# Top.net
KiCad netlist of a schematic drawn in Altium Designer
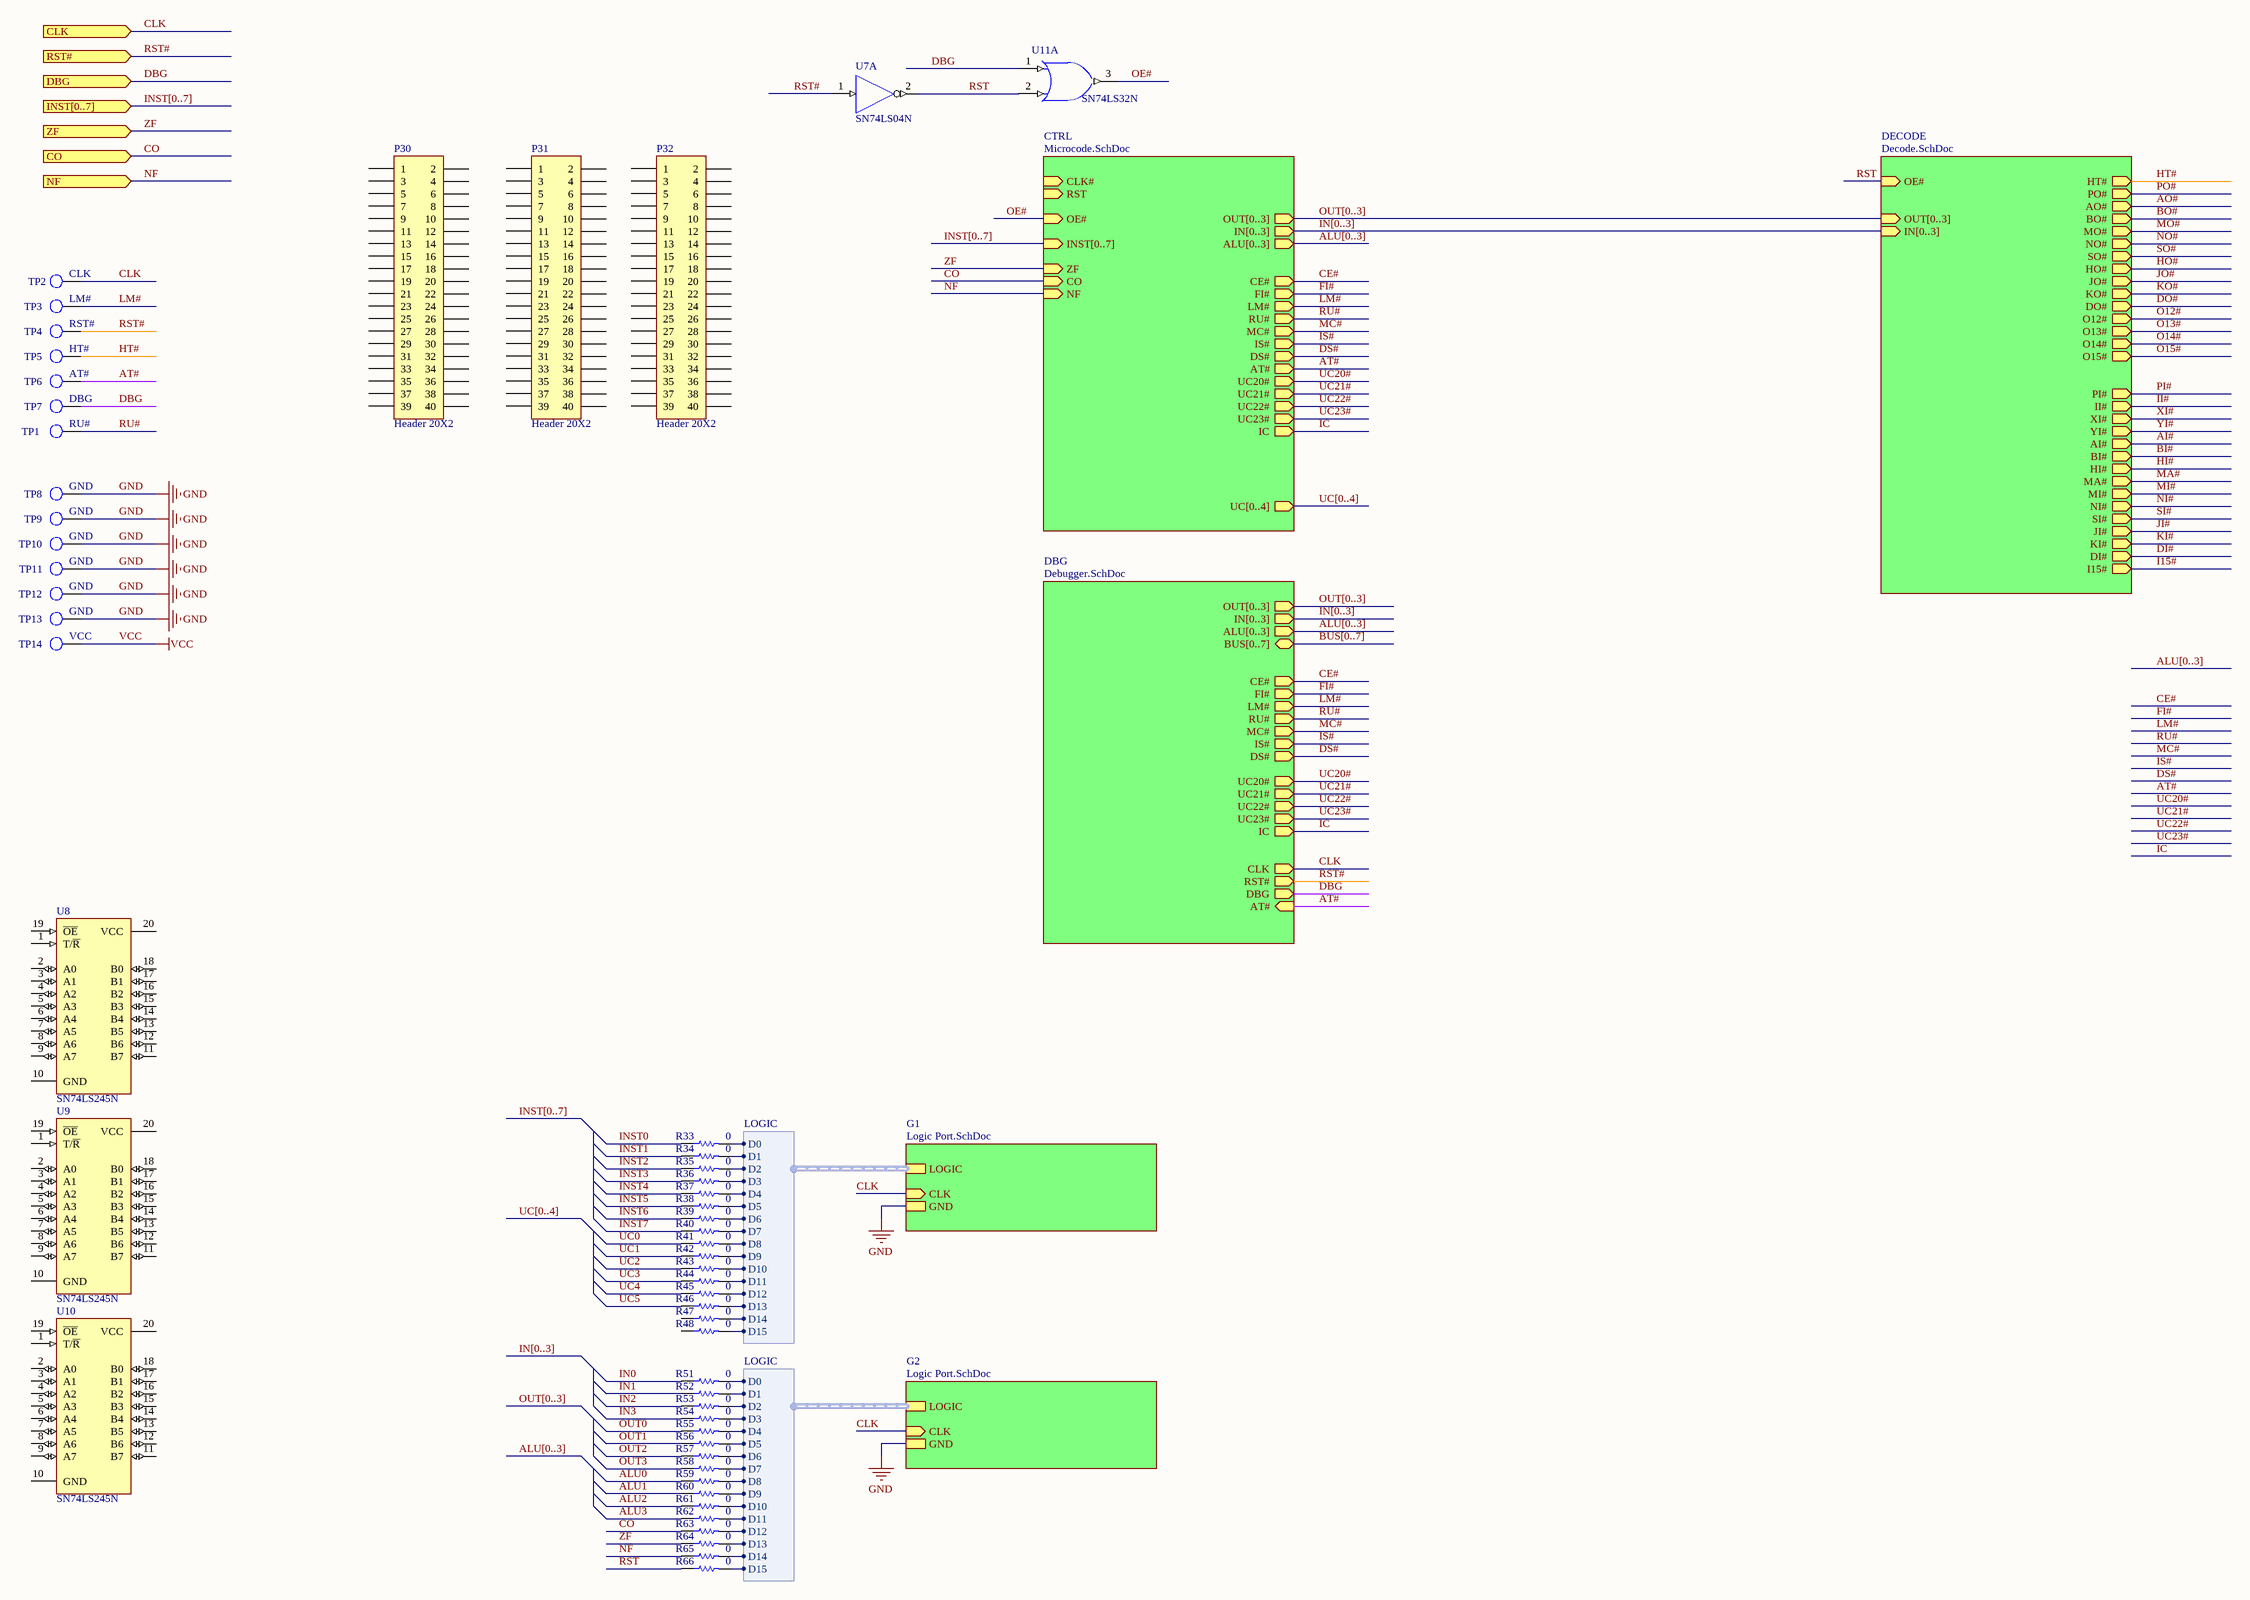
[diagram p0: Top.SchDoc]

(export (version "E")
  (design (tool "Eeschema 10.0.6"))
  (components
    (comp (ref "P30")
      (value "Header 20X2")
      (footprint "HDR2X20")
      (description "Header, 20-Pin, Dual row")
      (fields (field (name "PUBLISHER") "Altium Limited"))
      (libsource (lib "Miscellaneous Connectors") (part "Header 20X2"))
    )
    (comp (ref "P31")
      (value "Header 20X2")
      (footprint "HDR2X20")
      (description "Header, 20-Pin, Dual row")
      (fields (field (name "PUBLISHER") "Altium Limited"))
      (libsource (lib "Miscellaneous Connectors") (part "Header 20X2"))
    )
    (comp (ref "P32")
      (value "Header 20X2")
      (footprint "HDR2X20")
      (description "Header, 20-Pin, Dual row")
      (fields (field (name "PUBLISHER") "Altium Limited"))
      (libsource (lib "Miscellaneous Connectors") (part "Header 20X2"))
    )
    (comp (ref "R33")
      (value "0")
      (footprint "AXIAL-0.3")
      (description "Resistor")
      (fields (field (name "Comment") "Res1") (field (name "PUBLISHER") "Altium Limited"))
      (libsource (lib "Miscellaneous Devices") (part "Res1"))
    )
    (comp (ref "R34")
      (value "0")
      (footprint "AXIAL-0.3")
      (description "Resistor")
      (fields (field (name "Comment") "Res1") (field (name "PUBLISHER") "Altium Limited"))
      (libsource (lib "Miscellaneous Devices") (part "Res1"))
    )
    (comp (ref "R35")
      (value "0")
      (footprint "AXIAL-0.3")
      (description "Resistor")
      (fields (field (name "Comment") "Res1") (field (name "PUBLISHER") "Altium Limited"))
      (libsource (lib "Miscellaneous Devices") (part "Res1"))
    )
    (comp (ref "R36")
      (value "0")
      (footprint "AXIAL-0.3")
      (description "Resistor")
      (fields (field (name "Comment") "Res1") (field (name "PUBLISHER") "Altium Limited"))
      (libsource (lib "Miscellaneous Devices") (part "Res1"))
    )
    (comp (ref "R37")
      (value "0")
      (footprint "AXIAL-0.3")
      (description "Resistor")
      (fields (field (name "Comment") "Res1") (field (name "PUBLISHER") "Altium Limited"))
      (libsource (lib "Miscellaneous Devices") (part "Res1"))
    )
    (comp (ref "R38")
      (value "0")
      (footprint "AXIAL-0.3")
      (description "Resistor")
      (fields (field (name "Comment") "Res1") (field (name "PUBLISHER") "Altium Limited"))
      (libsource (lib "Miscellaneous Devices") (part "Res1"))
    )
    (comp (ref "R39")
      (value "0")
      (footprint "AXIAL-0.3")
      (description "Resistor")
      (fields (field (name "Comment") "Res1") (field (name "PUBLISHER") "Altium Limited"))
      (libsource (lib "Miscellaneous Devices") (part "Res1"))
    )
    (comp (ref "R40")
      (value "0")
      (footprint "AXIAL-0.3")
      (description "Resistor")
      (fields (field (name "Comment") "Res1") (field (name "PUBLISHER") "Altium Limited"))
      (libsource (lib "Miscellaneous Devices") (part "Res1"))
    )
    (comp (ref "R41")
      (value "0")
      (footprint "AXIAL-0.3")
      (description "Resistor")
      (fields (field (name "Comment") "Res1") (field (name "PUBLISHER") "Altium Limited"))
      (libsource (lib "Miscellaneous Devices") (part "Res1"))
    )
    (comp (ref "R42")
      (value "0")
      (footprint "AXIAL-0.3")
      (description "Resistor")
      (fields (field (name "Comment") "Res1") (field (name "PUBLISHER") "Altium Limited"))
      (libsource (lib "Miscellaneous Devices") (part "Res1"))
    )
    (comp (ref "R43")
      (value "0")
      (footprint "AXIAL-0.3")
      (description "Resistor")
      (fields (field (name "Comment") "Res1") (field (name "PUBLISHER") "Altium Limited"))
      (libsource (lib "Miscellaneous Devices") (part "Res1"))
    )
    (comp (ref "R44")
      (value "0")
      (footprint "AXIAL-0.3")
      (description "Resistor")
      (fields (field (name "Comment") "Res1") (field (name "PUBLISHER") "Altium Limited"))
      (libsource (lib "Miscellaneous Devices") (part "Res1"))
    )
    (comp (ref "R45")
      (value "0")
      (footprint "AXIAL-0.3")
      (description "Resistor")
      (fields (field (name "Comment") "Res1") (field (name "PUBLISHER") "Altium Limited"))
      (libsource (lib "Miscellaneous Devices") (part "Res1"))
    )
    (comp (ref "R46")
      (value "0")
      (footprint "AXIAL-0.3")
      (description "Resistor")
      (fields (field (name "Comment") "Res1") (field (name "PUBLISHER") "Altium Limited"))
      (libsource (lib "Miscellaneous Devices") (part "Res1"))
    )
    (comp (ref "R47")
      (value "0")
      (footprint "AXIAL-0.3")
      (description "Resistor")
      (fields (field (name "Comment") "Res1") (field (name "PUBLISHER") "Altium Limited"))
      (libsource (lib "Miscellaneous Devices") (part "Res1"))
    )
    (comp (ref "R48")
      (value "0")
      (footprint "AXIAL-0.3")
      (description "Resistor")
      (fields (field (name "Comment") "Res1") (field (name "PUBLISHER") "Altium Limited"))
      (libsource (lib "Miscellaneous Devices") (part "Res1"))
    )
    (comp (ref "R51")
      (value "0")
      (footprint "AXIAL-0.3")
      (description "Resistor")
      (fields (field (name "Comment") "Res1") (field (name "PUBLISHER") "Altium Limited"))
      (libsource (lib "Miscellaneous Devices") (part "Res1"))
    )
    (comp (ref "R52")
      (value "0")
      (footprint "AXIAL-0.3")
      (description "Resistor")
      (fields (field (name "Comment") "Res1") (field (name "PUBLISHER") "Altium Limited"))
      (libsource (lib "Miscellaneous Devices") (part "Res1"))
    )
    (comp (ref "R53")
      (value "0")
      (footprint "AXIAL-0.3")
      (description "Resistor")
      (fields (field (name "Comment") "Res1") (field (name "PUBLISHER") "Altium Limited"))
      (libsource (lib "Miscellaneous Devices") (part "Res1"))
    )
    (comp (ref "R54")
      (value "0")
      (footprint "AXIAL-0.3")
      (description "Resistor")
      (fields (field (name "Comment") "Res1") (field (name "PUBLISHER") "Altium Limited"))
      (libsource (lib "Miscellaneous Devices") (part "Res1"))
    )
    (comp (ref "R55")
      (value "0")
      (footprint "AXIAL-0.3")
      (description "Resistor")
      (fields (field (name "Comment") "Res1") (field (name "PUBLISHER") "Altium Limited"))
      (libsource (lib "Miscellaneous Devices") (part "Res1"))
    )
    (comp (ref "R56")
      (value "0")
      (footprint "AXIAL-0.3")
      (description "Resistor")
      (fields (field (name "Comment") "Res1") (field (name "PUBLISHER") "Altium Limited"))
      (libsource (lib "Miscellaneous Devices") (part "Res1"))
    )
    (comp (ref "R57")
      (value "0")
      (footprint "AXIAL-0.3")
      (description "Resistor")
      (fields (field (name "Comment") "Res1") (field (name "PUBLISHER") "Altium Limited"))
      (libsource (lib "Miscellaneous Devices") (part "Res1"))
    )
    (comp (ref "R58")
      (value "0")
      (footprint "AXIAL-0.3")
      (description "Resistor")
      (fields (field (name "Comment") "Res1") (field (name "PUBLISHER") "Altium Limited"))
      (libsource (lib "Miscellaneous Devices") (part "Res1"))
    )
    (comp (ref "R59")
      (value "0")
      (footprint "AXIAL-0.3")
      (description "Resistor")
      (fields (field (name "Comment") "Res1") (field (name "PUBLISHER") "Altium Limited"))
      (libsource (lib "Miscellaneous Devices") (part "Res1"))
    )
    (comp (ref "R60")
      (value "0")
      (footprint "AXIAL-0.3")
      (description "Resistor")
      (fields (field (name "Comment") "Res1") (field (name "PUBLISHER") "Altium Limited"))
      (libsource (lib "Miscellaneous Devices") (part "Res1"))
    )
    (comp (ref "R61")
      (value "0")
      (footprint "AXIAL-0.3")
      (description "Resistor")
      (fields (field (name "Comment") "Res1") (field (name "PUBLISHER") "Altium Limited"))
      (libsource (lib "Miscellaneous Devices") (part "Res1"))
    )
    (comp (ref "R62")
      (value "0")
      (footprint "AXIAL-0.3")
      (description "Resistor")
      (fields (field (name "Comment") "Res1") (field (name "PUBLISHER") "Altium Limited"))
      (libsource (lib "Miscellaneous Devices") (part "Res1"))
    )
    (comp (ref "R63")
      (value "0")
      (footprint "AXIAL-0.3")
      (description "Resistor")
      (fields (field (name "Comment") "Res1") (field (name "PUBLISHER") "Altium Limited"))
      (libsource (lib "Miscellaneous Devices") (part "Res1"))
    )
    (comp (ref "R64")
      (value "0")
      (footprint "AXIAL-0.3")
      (description "Resistor")
      (fields (field (name "Comment") "Res1") (field (name "PUBLISHER") "Altium Limited"))
      (libsource (lib "Miscellaneous Devices") (part "Res1"))
    )
    (comp (ref "R65")
      (value "0")
      (footprint "AXIAL-0.3")
      (description "Resistor")
      (fields (field (name "Comment") "Res1") (field (name "PUBLISHER") "Altium Limited"))
      (libsource (lib "Miscellaneous Devices") (part "Res1"))
    )
    (comp (ref "R66")
      (value "0")
      (footprint "AXIAL-0.3")
      (description "Resistor")
      (fields (field (name "Comment") "Res1") (field (name "PUBLISHER") "Altium Limited"))
      (libsource (lib "Miscellaneous Devices") (part "Res1"))
    )
    (comp (ref "TP1") (value "RU#") (footprint "KSTN-5011_V") (libsource (lib "TP") (part "TP")))
    (comp (ref "TP2") (value "CLK") (footprint "KSTN-5011_V") (libsource (lib "TP") (part "TP")))
    (comp (ref "TP3") (value "LM#") (footprint "KSTN-5011_V") (libsource (lib "TP") (part "TP")))
    (comp (ref "TP4") (value "RST#") (footprint "KSTN-5011_V") (libsource (lib "TP") (part "TP")))
    (comp (ref "TP5") (value "HT#") (footprint "KSTN-5011_V") (libsource (lib "TP") (part "TP")))
    (comp (ref "TP6") (value "AT#") (footprint "KSTN-5011_V") (libsource (lib "TP") (part "TP")))
    (comp (ref "TP7") (value "DBG") (footprint "KSTN-5011_V") (libsource (lib "TP") (part "TP")))
    (comp (ref "TP8") (value "GND") (footprint "KSTN-5011_V") (libsource (lib "TP") (part "TP")))
    (comp (ref "TP9") (value "GND") (footprint "KSTN-5011_V") (libsource (lib "TP") (part "TP")))
    (comp (ref "TP10") (value "GND") (footprint "KSTN-5011_V") (libsource (lib "TP") (part "TP")))
    (comp (ref "TP11") (value "GND") (footprint "KSTN-5011_V") (libsource (lib "TP") (part "TP")))
    (comp (ref "TP12") (value "GND") (footprint "KSTN-5011_V") (libsource (lib "TP") (part "TP")))
    (comp (ref "TP13") (value "GND") (footprint "KSTN-5011_V") (libsource (lib "TP") (part "TP")))
    (comp (ref "TP14") (value "VCC") (footprint "KSTN-5011_V") (libsource (lib "TP") (part "TP")))
    (comp (ref "U7")
      (value "SN74LS04N")
      (footprint "N014")
      (description "Hex Inverter")
      (fields (field (name "PUBLISHER") "Altium Limited"))
      (libsource (lib "TI Logic Gate 2") (part "SN74LS04N"))
    )
    (comp (ref "U8")
      (value "SN74LS245N")
      (footprint "N020")
      (description "Octal Bus Transceiver with 3-State Outputs")
      (fields (field (name "PUBLISHER") "Altium Limited"))
      (libsource (lib "TI Interface 8-Bit Line Transceiver") (part "SN74LS245N"))
    )
    (comp (ref "U9")
      (value "SN74LS245N")
      (footprint "N020")
      (description "Octal Bus Transceiver with 3-State Outputs")
      (fields (field (name "PUBLISHER") "Altium Limited"))
      (libsource (lib "TI Interface 8-Bit Line Transceiver") (part "SN74LS245N"))
    )
    (comp (ref "U10")
      (value "SN74LS245N")
      (footprint "N020")
      (description "Octal Bus Transceiver with 3-State Outputs")
      (fields (field (name "PUBLISHER") "Altium Limited"))
      (libsource (lib "TI Interface 8-Bit Line Transceiver") (part "SN74LS245N"))
    )
    (comp (ref "U11")
      (value "SN74LS32N")
      (footprint "N014")
      (description "Quadruple 2-Input Positive-OR Gate")
      (fields (field (name "PUBLISHER") "Altium Limited"))
      (libsource (lib "TI Logic Gate 2") (part "SN74LS32N"))
    )
  )
  (nets
    (net (code "11") (name "/ALU0") (class "Default")
      (node (ref "R59") (pin "1") (pinfunction "1_1") (pintype "passive"))
    )
    (net (code "12") (name "/ALU1") (class "Default")
      (node (ref "R60") (pin "1") (pinfunction "1_1") (pintype "passive"))
    )
    (net (code "13") (name "/ALU2") (class "Default")
      (node (ref "R61") (pin "1") (pinfunction "1_1") (pintype "passive"))
    )
    (net (code "14") (name "/ALU3") (class "Default")
      (node (ref "R62") (pin "1") (pinfunction "1_1") (pintype "passive"))
    )
    (net (code "17") (name "/AT#") (class "Default") (node (ref "TP6") (pin "1") (pintype "passive")))
    (net (code "22") (name "/CLK") (class "Default") (node (ref "TP2") (pin "1") (pintype "passive")))
    (net (code "24") (name "/CO") (class "Default")
      (node (ref "R63") (pin "1") (pinfunction "1_1") (pintype "passive"))
    )
    (net (code "25") (name "/DBG") (class "Default")
      (node (ref "TP7") (pin "1") (pintype "passive"))
      (node (ref "U11") (pin "1") (pinfunction "A_1") (pintype "input"))
    )
    (net (code "32") (name "/HT#") (class "Default") (node (ref "TP5") (pin "1") (pintype "passive")))
    (net (code "36") (name "/IN0") (class "Default")
      (node (ref "R51") (pin "1") (pinfunction "1_1") (pintype "passive"))
    )
    (net (code "37") (name "/IN1") (class "Default")
      (node (ref "R52") (pin "1") (pinfunction "1_1") (pintype "passive"))
    )
    (net (code "38") (name "/IN2") (class "Default")
      (node (ref "R53") (pin "1") (pinfunction "1_1") (pintype "passive"))
    )
    (net (code "39") (name "/IN3") (class "Default")
      (node (ref "R54") (pin "1") (pinfunction "1_1") (pintype "passive"))
    )
    (net (code "40") (name "/INST0") (class "Default")
      (node (ref "R33") (pin "1") (pinfunction "1_1") (pintype "passive"))
    )
    (net (code "41") (name "/INST1") (class "Default")
      (node (ref "R34") (pin "1") (pinfunction "1_1") (pintype "passive"))
    )
    (net (code "42") (name "/INST2") (class "Default")
      (node (ref "R35") (pin "1") (pinfunction "1_1") (pintype "passive"))
    )
    (net (code "43") (name "/INST3") (class "Default")
      (node (ref "R36") (pin "1") (pinfunction "1_1") (pintype "passive"))
    )
    (net (code "44") (name "/INST4") (class "Default")
      (node (ref "R37") (pin "1") (pinfunction "1_1") (pintype "passive"))
    )
    (net (code "45") (name "/INST5") (class "Default")
      (node (ref "R38") (pin "1") (pinfunction "1_1") (pintype "passive"))
    )
    (net (code "46") (name "/INST6") (class "Default")
      (node (ref "R39") (pin "1") (pinfunction "1_1") (pintype "passive"))
    )
    (net (code "47") (name "/INST7") (class "Default")
      (node (ref "R40") (pin "1") (pinfunction "1_1") (pintype "passive"))
    )
    (net (code "55") (name "/LM#") (class "Default") (node (ref "TP3") (pin "1") (pintype "passive")))
    (net (code "60") (name "/NF") (class "Default")
      (node (ref "R65") (pin "1") (pinfunction "1_1") (pintype "passive"))
    )
    (net (code "67") (name "/OE#") (class "Default")
      (node (ref "U11") (pin "3") (pinfunction "Y_3") (pintype "output"))
    )
    (net (code "68") (name "/OUT0") (class "Default")
      (node (ref "R55") (pin "1") (pinfunction "1_1") (pintype "passive"))
    )
    (net (code "69") (name "/OUT1") (class "Default")
      (node (ref "R56") (pin "1") (pinfunction "1_1") (pintype "passive"))
    )
    (net (code "70") (name "/OUT2") (class "Default")
      (node (ref "R57") (pin "1") (pinfunction "1_1") (pintype "passive"))
    )
    (net (code "71") (name "/OUT3") (class "Default")
      (node (ref "R58") (pin "1") (pinfunction "1_1") (pintype "passive"))
    )
    (net (code "75") (name "/RST") (class "Default")
      (node (ref "R66") (pin "1") (pinfunction "1_1") (pintype "passive"))
      (node (ref "U11") (pin "2") (pinfunction "B_2") (pintype "input"))
      (node (ref "U7") (pin "2") (pinfunction "Y_2") (pintype "output"))
    )
    (net (code "76") (name "/RST#") (class "Default")
      (node (ref "TP4") (pin "1") (pintype "passive"))
      (node (ref "U7") (pin "1") (pinfunction "A_1") (pintype "input"))
    )
    (net (code "78") (name "/RU#") (class "Default") (node (ref "TP1") (pin "1") (pintype "passive")))
    (net (code "81") (name "/UC0") (class "Default")
      (node (ref "R41") (pin "1") (pinfunction "1_1") (pintype "passive"))
    )
    (net (code "82") (name "/UC1") (class "Default")
      (node (ref "R42") (pin "1") (pinfunction "1_1") (pintype "passive"))
    )
    (net (code "83") (name "/UC2") (class "Default")
      (node (ref "R43") (pin "1") (pinfunction "1_1") (pintype "passive"))
    )
    (net (code "84") (name "/UC3") (class "Default")
      (node (ref "R44") (pin "1") (pinfunction "1_1") (pintype "passive"))
    )
    (net (code "85") (name "/UC4") (class "Default")
      (node (ref "R45") (pin "1") (pinfunction "1_1") (pintype "passive"))
    )
    (net (code "86") (name "/UC5") (class "Default")
      (node (ref "R46") (pin "1") (pinfunction "1_1") (pintype "passive"))
    )
    (net (code "94") (name "/ZF") (class "Default")
      (node (ref "R64") (pin "1") (pinfunction "1_1") (pintype "passive"))
    )
    (net (code "96") (name "GND") (class "Default")
      (node (ref "TP10") (pin "1") (pintype "passive"))
      (node (ref "TP11") (pin "1") (pintype "passive"))
      (node (ref "TP12") (pin "1") (pintype "passive"))
      (node (ref "TP13") (pin "1") (pintype "passive"))
      (node (ref "TP8") (pin "1") (pintype "passive"))
      (node (ref "TP9") (pin "1") (pintype "passive"))
      (node (ref "U11") (pin "7") (pinfunction "GND_7") (pintype "power_in"))
      (node (ref "U7") (pin "7") (pinfunction "GND_7") (pintype "power_in"))
    )
    (net (code "97") (name "VCC") (class "Default")
      (node (ref "TP14") (pin "1") (pintype "passive"))
      (node (ref "U11") (pin "14") (pinfunction "VCC_14") (pintype "power_in"))
      (node (ref "U7") (pin "14") (pinfunction "VCC_14") (pintype "power_in"))
    )
    (net (code "98") (name "unconnected-(P30-Pad1)") (class "Default")
      (node (ref "P30") (pin "1") (pinfunction "1_1") (pintype "passive"))
    )
    (net (code "99") (name "unconnected-(P30-Pad2)") (class "Default")
      (node (ref "P30") (pin "2") (pinfunction "2_2") (pintype "passive"))
    )
    (net (code "100") (name "unconnected-(P30-Pad3)") (class "Default")
      (node (ref "P30") (pin "3") (pinfunction "3_3") (pintype "passive"))
    )
    (net (code "101") (name "unconnected-(P30-Pad4)") (class "Default")
      (node (ref "P30") (pin "4") (pinfunction "4_4") (pintype "passive"))
    )
    (net (code "102") (name "unconnected-(P30-Pad5)") (class "Default")
      (node (ref "P30") (pin "5") (pinfunction "5_5") (pintype "passive"))
    )
    (net (code "103") (name "unconnected-(P30-Pad6)") (class "Default")
      (node (ref "P30") (pin "6") (pinfunction "6_6") (pintype "passive"))
    )
    (net (code "104") (name "unconnected-(P30-Pad7)") (class "Default")
      (node (ref "P30") (pin "7") (pinfunction "7_7") (pintype "passive"))
    )
    (net (code "105") (name "unconnected-(P30-Pad8)") (class "Default")
      (node (ref "P30") (pin "8") (pinfunction "8_8") (pintype "passive"))
    )
    (net (code "106") (name "unconnected-(P30-Pad9)") (class "Default")
      (node (ref "P30") (pin "9") (pinfunction "9_9") (pintype "passive"))
    )
    (net (code "107") (name "unconnected-(P30-Pad10)") (class "Default")
      (node (ref "P30") (pin "10") (pinfunction "10_10") (pintype "passive"))
    )
    (net (code "108") (name "unconnected-(P30-Pad11)") (class "Default")
      (node (ref "P30") (pin "11") (pinfunction "11_11") (pintype "passive"))
    )
    (net (code "109") (name "unconnected-(P30-Pad12)") (class "Default")
      (node (ref "P30") (pin "12") (pinfunction "12_12") (pintype "passive"))
    )
    (net (code "110") (name "unconnected-(P30-Pad13)") (class "Default")
      (node (ref "P30") (pin "13") (pinfunction "13_13") (pintype "passive"))
    )
    (net (code "111") (name "unconnected-(P30-Pad14)") (class "Default")
      (node (ref "P30") (pin "14") (pinfunction "14_14") (pintype "passive"))
    )
    (net (code "112") (name "unconnected-(P30-Pad15)") (class "Default")
      (node (ref "P30") (pin "15") (pinfunction "15_15") (pintype "passive"))
    )
    (net (code "113") (name "unconnected-(P30-Pad16)") (class "Default")
      (node (ref "P30") (pin "16") (pinfunction "16_16") (pintype "passive"))
    )
    (net (code "114") (name "unconnected-(P30-Pad17)") (class "Default")
      (node (ref "P30") (pin "17") (pinfunction "17_17") (pintype "passive"))
    )
    (net (code "115") (name "unconnected-(P30-Pad18)") (class "Default")
      (node (ref "P30") (pin "18") (pinfunction "18_18") (pintype "passive"))
    )
    (net (code "116") (name "unconnected-(P30-Pad19)") (class "Default")
      (node (ref "P30") (pin "19") (pinfunction "19_19") (pintype "passive"))
    )
    (net (code "117") (name "unconnected-(P30-Pad20)") (class "Default")
      (node (ref "P30") (pin "20") (pinfunction "20_20") (pintype "passive"))
    )
    (net (code "118") (name "unconnected-(P30-Pad21)") (class "Default")
      (node (ref "P30") (pin "21") (pinfunction "21_21") (pintype "passive"))
    )
    (net (code "119") (name "unconnected-(P30-Pad22)") (class "Default")
      (node (ref "P30") (pin "22") (pinfunction "22_22") (pintype "passive"))
    )
    (net (code "120") (name "unconnected-(P30-Pad23)") (class "Default")
      (node (ref "P30") (pin "23") (pinfunction "23_23") (pintype "passive"))
    )
    (net (code "121") (name "unconnected-(P30-Pad24)") (class "Default")
      (node (ref "P30") (pin "24") (pinfunction "24_24") (pintype "passive"))
    )
    (net (code "122") (name "unconnected-(P30-Pad25)") (class "Default")
      (node (ref "P30") (pin "25") (pinfunction "25_25") (pintype "passive"))
    )
    (net (code "123") (name "unconnected-(P30-Pad26)") (class "Default")
      (node (ref "P30") (pin "26") (pinfunction "26_26") (pintype "passive"))
    )
    (net (code "124") (name "unconnected-(P30-Pad27)") (class "Default")
      (node (ref "P30") (pin "27") (pinfunction "27_27") (pintype "passive"))
    )
    (net (code "125") (name "unconnected-(P30-Pad28)") (class "Default")
      (node (ref "P30") (pin "28") (pinfunction "28_28") (pintype "passive"))
    )
    (net (code "126") (name "unconnected-(P30-Pad29)") (class "Default")
      (node (ref "P30") (pin "29") (pinfunction "29_29") (pintype "passive"))
    )
    (net (code "127") (name "unconnected-(P30-Pad30)") (class "Default")
      (node (ref "P30") (pin "30") (pinfunction "30_30") (pintype "passive"))
    )
    (net (code "128") (name "unconnected-(P30-Pad31)") (class "Default")
      (node (ref "P30") (pin "31") (pinfunction "31_31") (pintype "passive"))
    )
    (net (code "129") (name "unconnected-(P30-Pad32)") (class "Default")
      (node (ref "P30") (pin "32") (pinfunction "32_32") (pintype "passive"))
    )
    (net (code "130") (name "unconnected-(P30-Pad33)") (class "Default")
      (node (ref "P30") (pin "33") (pinfunction "33_33") (pintype "passive"))
    )
    (net (code "131") (name "unconnected-(P30-Pad34)") (class "Default")
      (node (ref "P30") (pin "34") (pinfunction "34_34") (pintype "passive"))
    )
    (net (code "132") (name "unconnected-(P30-Pad35)") (class "Default")
      (node (ref "P30") (pin "35") (pinfunction "35_35") (pintype "passive"))
    )
    (net (code "133") (name "unconnected-(P30-Pad36)") (class "Default")
      (node (ref "P30") (pin "36") (pinfunction "36_36") (pintype "passive"))
    )
    (net (code "134") (name "unconnected-(P30-Pad37)") (class "Default")
      (node (ref "P30") (pin "37") (pinfunction "37_37") (pintype "passive"))
    )
    (net (code "135") (name "unconnected-(P30-Pad38)") (class "Default")
      (node (ref "P30") (pin "38") (pinfunction "38_38") (pintype "passive"))
    )
    (net (code "136") (name "unconnected-(P30-Pad39)") (class "Default")
      (node (ref "P30") (pin "39") (pinfunction "39_39") (pintype "passive"))
    )
    (net (code "137") (name "unconnected-(P30-Pad40)") (class "Default")
      (node (ref "P30") (pin "40") (pinfunction "40_40") (pintype "passive"))
    )
    (net (code "138") (name "unconnected-(P31-Pad1)") (class "Default")
      (node (ref "P31") (pin "1") (pinfunction "1_1") (pintype "passive"))
    )
    (net (code "139") (name "unconnected-(P31-Pad2)") (class "Default")
      (node (ref "P31") (pin "2") (pinfunction "2_2") (pintype "passive"))
    )
    (net (code "140") (name "unconnected-(P31-Pad3)") (class "Default")
      (node (ref "P31") (pin "3") (pinfunction "3_3") (pintype "passive"))
    )
    (net (code "141") (name "unconnected-(P31-Pad4)") (class "Default")
      (node (ref "P31") (pin "4") (pinfunction "4_4") (pintype "passive"))
    )
    (net (code "142") (name "unconnected-(P31-Pad5)") (class "Default")
      (node (ref "P31") (pin "5") (pinfunction "5_5") (pintype "passive"))
    )
    (net (code "143") (name "unconnected-(P31-Pad6)") (class "Default")
      (node (ref "P31") (pin "6") (pinfunction "6_6") (pintype "passive"))
    )
    (net (code "144") (name "unconnected-(P31-Pad7)") (class "Default")
      (node (ref "P31") (pin "7") (pinfunction "7_7") (pintype "passive"))
    )
    (net (code "145") (name "unconnected-(P31-Pad8)") (class "Default")
      (node (ref "P31") (pin "8") (pinfunction "8_8") (pintype "passive"))
    )
    (net (code "146") (name "unconnected-(P31-Pad9)") (class "Default")
      (node (ref "P31") (pin "9") (pinfunction "9_9") (pintype "passive"))
    )
    (net (code "147") (name "unconnected-(P31-Pad10)") (class "Default")
      (node (ref "P31") (pin "10") (pinfunction "10_10") (pintype "passive"))
    )
    (net (code "148") (name "unconnected-(P31-Pad11)") (class "Default")
      (node (ref "P31") (pin "11") (pinfunction "11_11") (pintype "passive"))
    )
    (net (code "149") (name "unconnected-(P31-Pad12)") (class "Default")
      (node (ref "P31") (pin "12") (pinfunction "12_12") (pintype "passive"))
    )
    (net (code "150") (name "unconnected-(P31-Pad13)") (class "Default")
      (node (ref "P31") (pin "13") (pinfunction "13_13") (pintype "passive"))
    )
    (net (code "151") (name "unconnected-(P31-Pad14)") (class "Default")
      (node (ref "P31") (pin "14") (pinfunction "14_14") (pintype "passive"))
    )
    (net (code "152") (name "unconnected-(P31-Pad15)") (class "Default")
      (node (ref "P31") (pin "15") (pinfunction "15_15") (pintype "passive"))
    )
    (net (code "153") (name "unconnected-(P31-Pad16)") (class "Default")
      (node (ref "P31") (pin "16") (pinfunction "16_16") (pintype "passive"))
    )
    (net (code "154") (name "unconnected-(P31-Pad17)") (class "Default")
      (node (ref "P31") (pin "17") (pinfunction "17_17") (pintype "passive"))
    )
    (net (code "155") (name "unconnected-(P31-Pad18)") (class "Default")
      (node (ref "P31") (pin "18") (pinfunction "18_18") (pintype "passive"))
    )
    (net (code "156") (name "unconnected-(P31-Pad19)") (class "Default")
      (node (ref "P31") (pin "19") (pinfunction "19_19") (pintype "passive"))
    )
    (net (code "157") (name "unconnected-(P31-Pad20)") (class "Default")
      (node (ref "P31") (pin "20") (pinfunction "20_20") (pintype "passive"))
    )
    (net (code "158") (name "unconnected-(P31-Pad21)") (class "Default")
      (node (ref "P31") (pin "21") (pinfunction "21_21") (pintype "passive"))
    )
    (net (code "159") (name "unconnected-(P31-Pad22)") (class "Default")
      (node (ref "P31") (pin "22") (pinfunction "22_22") (pintype "passive"))
    )
    (net (code "160") (name "unconnected-(P31-Pad23)") (class "Default")
      (node (ref "P31") (pin "23") (pinfunction "23_23") (pintype "passive"))
    )
    (net (code "161") (name "unconnected-(P31-Pad24)") (class "Default")
      (node (ref "P31") (pin "24") (pinfunction "24_24") (pintype "passive"))
    )
    (net (code "162") (name "unconnected-(P31-Pad25)") (class "Default")
      (node (ref "P31") (pin "25") (pinfunction "25_25") (pintype "passive"))
    )
    (net (code "163") (name "unconnected-(P31-Pad26)") (class "Default")
      (node (ref "P31") (pin "26") (pinfunction "26_26") (pintype "passive"))
    )
    (net (code "164") (name "unconnected-(P31-Pad27)") (class "Default")
      (node (ref "P31") (pin "27") (pinfunction "27_27") (pintype "passive"))
    )
    (net (code "165") (name "unconnected-(P31-Pad28)") (class "Default")
      (node (ref "P31") (pin "28") (pinfunction "28_28") (pintype "passive"))
    )
    (net (code "166") (name "unconnected-(P31-Pad29)") (class "Default")
      (node (ref "P31") (pin "29") (pinfunction "29_29") (pintype "passive"))
    )
    (net (code "167") (name "unconnected-(P31-Pad30)") (class "Default")
      (node (ref "P31") (pin "30") (pinfunction "30_30") (pintype "passive"))
    )
    (net (code "168") (name "unconnected-(P31-Pad31)") (class "Default")
      (node (ref "P31") (pin "31") (pinfunction "31_31") (pintype "passive"))
    )
    (net (code "169") (name "unconnected-(P31-Pad32)") (class "Default")
      (node (ref "P31") (pin "32") (pinfunction "32_32") (pintype "passive"))
    )
    (net (code "170") (name "unconnected-(P31-Pad33)") (class "Default")
      (node (ref "P31") (pin "33") (pinfunction "33_33") (pintype "passive"))
    )
    (net (code "171") (name "unconnected-(P31-Pad34)") (class "Default")
      (node (ref "P31") (pin "34") (pinfunction "34_34") (pintype "passive"))
    )
    (net (code "172") (name "unconnected-(P31-Pad35)") (class "Default")
      (node (ref "P31") (pin "35") (pinfunction "35_35") (pintype "passive"))
    )
    (net (code "173") (name "unconnected-(P31-Pad36)") (class "Default")
      (node (ref "P31") (pin "36") (pinfunction "36_36") (pintype "passive"))
    )
    (net (code "174") (name "unconnected-(P31-Pad37)") (class "Default")
      (node (ref "P31") (pin "37") (pinfunction "37_37") (pintype "passive"))
    )
    (net (code "175") (name "unconnected-(P31-Pad38)") (class "Default")
      (node (ref "P31") (pin "38") (pinfunction "38_38") (pintype "passive"))
    )
    (net (code "176") (name "unconnected-(P31-Pad39)") (class "Default")
      (node (ref "P31") (pin "39") (pinfunction "39_39") (pintype "passive"))
    )
    (net (code "177") (name "unconnected-(P31-Pad40)") (class "Default")
      (node (ref "P31") (pin "40") (pinfunction "40_40") (pintype "passive"))
    )
    (net (code "178") (name "unconnected-(P32-Pad1)") (class "Default")
      (node (ref "P32") (pin "1") (pinfunction "1_1") (pintype "passive"))
    )
    (net (code "179") (name "unconnected-(P32-Pad2)") (class "Default")
      (node (ref "P32") (pin "2") (pinfunction "2_2") (pintype "passive"))
    )
    (net (code "180") (name "unconnected-(P32-Pad3)") (class "Default")
      (node (ref "P32") (pin "3") (pinfunction "3_3") (pintype "passive"))
    )
    (net (code "181") (name "unconnected-(P32-Pad4)") (class "Default")
      (node (ref "P32") (pin "4") (pinfunction "4_4") (pintype "passive"))
    )
    (net (code "182") (name "unconnected-(P32-Pad5)") (class "Default")
      (node (ref "P32") (pin "5") (pinfunction "5_5") (pintype "passive"))
    )
    (net (code "183") (name "unconnected-(P32-Pad6)") (class "Default")
      (node (ref "P32") (pin "6") (pinfunction "6_6") (pintype "passive"))
    )
    (net (code "184") (name "unconnected-(P32-Pad7)") (class "Default")
      (node (ref "P32") (pin "7") (pinfunction "7_7") (pintype "passive"))
    )
    (net (code "185") (name "unconnected-(P32-Pad8)") (class "Default")
      (node (ref "P32") (pin "8") (pinfunction "8_8") (pintype "passive"))
    )
    (net (code "186") (name "unconnected-(P32-Pad9)") (class "Default")
      (node (ref "P32") (pin "9") (pinfunction "9_9") (pintype "passive"))
    )
    (net (code "187") (name "unconnected-(P32-Pad10)") (class "Default")
      (node (ref "P32") (pin "10") (pinfunction "10_10") (pintype "passive"))
    )
    (net (code "188") (name "unconnected-(P32-Pad11)") (class "Default")
      (node (ref "P32") (pin "11") (pinfunction "11_11") (pintype "passive"))
    )
    (net (code "189") (name "unconnected-(P32-Pad12)") (class "Default")
      (node (ref "P32") (pin "12") (pinfunction "12_12") (pintype "passive"))
    )
    (net (code "190") (name "unconnected-(P32-Pad13)") (class "Default")
      (node (ref "P32") (pin "13") (pinfunction "13_13") (pintype "passive"))
    )
    (net (code "191") (name "unconnected-(P32-Pad14)") (class "Default")
      (node (ref "P32") (pin "14") (pinfunction "14_14") (pintype "passive"))
    )
    (net (code "192") (name "unconnected-(P32-Pad15)") (class "Default")
      (node (ref "P32") (pin "15") (pinfunction "15_15") (pintype "passive"))
    )
    (net (code "193") (name "unconnected-(P32-Pad16)") (class "Default")
      (node (ref "P32") (pin "16") (pinfunction "16_16") (pintype "passive"))
    )
    (net (code "194") (name "unconnected-(P32-Pad17)") (class "Default")
      (node (ref "P32") (pin "17") (pinfunction "17_17") (pintype "passive"))
    )
    (net (code "195") (name "unconnected-(P32-Pad18)") (class "Default")
      (node (ref "P32") (pin "18") (pinfunction "18_18") (pintype "passive"))
    )
    (net (code "196") (name "unconnected-(P32-Pad19)") (class "Default")
      (node (ref "P32") (pin "19") (pinfunction "19_19") (pintype "passive"))
    )
    (net (code "197") (name "unconnected-(P32-Pad20)") (class "Default")
      (node (ref "P32") (pin "20") (pinfunction "20_20") (pintype "passive"))
    )
    (net (code "198") (name "unconnected-(P32-Pad21)") (class "Default")
      (node (ref "P32") (pin "21") (pinfunction "21_21") (pintype "passive"))
    )
    (net (code "199") (name "unconnected-(P32-Pad22)") (class "Default")
      (node (ref "P32") (pin "22") (pinfunction "22_22") (pintype "passive"))
    )
    (net (code "200") (name "unconnected-(P32-Pad23)") (class "Default")
      (node (ref "P32") (pin "23") (pinfunction "23_23") (pintype "passive"))
    )
    (net (code "201") (name "unconnected-(P32-Pad24)") (class "Default")
      (node (ref "P32") (pin "24") (pinfunction "24_24") (pintype "passive"))
    )
    (net (code "202") (name "unconnected-(P32-Pad25)") (class "Default")
      (node (ref "P32") (pin "25") (pinfunction "25_25") (pintype "passive"))
    )
    (net (code "203") (name "unconnected-(P32-Pad26)") (class "Default")
      (node (ref "P32") (pin "26") (pinfunction "26_26") (pintype "passive"))
    )
    (net (code "204") (name "unconnected-(P32-Pad27)") (class "Default")
      (node (ref "P32") (pin "27") (pinfunction "27_27") (pintype "passive"))
    )
    (net (code "205") (name "unconnected-(P32-Pad28)") (class "Default")
      (node (ref "P32") (pin "28") (pinfunction "28_28") (pintype "passive"))
    )
    (net (code "206") (name "unconnected-(P32-Pad29)") (class "Default")
      (node (ref "P32") (pin "29") (pinfunction "29_29") (pintype "passive"))
    )
    (net (code "207") (name "unconnected-(P32-Pad30)") (class "Default")
      (node (ref "P32") (pin "30") (pinfunction "30_30") (pintype "passive"))
    )
    (net (code "208") (name "unconnected-(P32-Pad31)") (class "Default")
      (node (ref "P32") (pin "31") (pinfunction "31_31") (pintype "passive"))
    )
    (net (code "209") (name "unconnected-(P32-Pad32)") (class "Default")
      (node (ref "P32") (pin "32") (pinfunction "32_32") (pintype "passive"))
    )
    (net (code "210") (name "unconnected-(P32-Pad33)") (class "Default")
      (node (ref "P32") (pin "33") (pinfunction "33_33") (pintype "passive"))
    )
    (net (code "211") (name "unconnected-(P32-Pad34)") (class "Default")
      (node (ref "P32") (pin "34") (pinfunction "34_34") (pintype "passive"))
    )
    (net (code "212") (name "unconnected-(P32-Pad35)") (class "Default")
      (node (ref "P32") (pin "35") (pinfunction "35_35") (pintype "passive"))
    )
    (net (code "213") (name "unconnected-(P32-Pad36)") (class "Default")
      (node (ref "P32") (pin "36") (pinfunction "36_36") (pintype "passive"))
    )
    (net (code "214") (name "unconnected-(P32-Pad37)") (class "Default")
      (node (ref "P32") (pin "37") (pinfunction "37_37") (pintype "passive"))
    )
    (net (code "215") (name "unconnected-(P32-Pad38)") (class "Default")
      (node (ref "P32") (pin "38") (pinfunction "38_38") (pintype "passive"))
    )
    (net (code "216") (name "unconnected-(P32-Pad39)") (class "Default")
      (node (ref "P32") (pin "39") (pinfunction "39_39") (pintype "passive"))
    )
    (net (code "217") (name "unconnected-(P32-Pad40)") (class "Default")
      (node (ref "P32") (pin "40") (pinfunction "40_40") (pintype "passive"))
    )
    (net (code "218") (name "unconnected-(R33-Pad2)") (class "Default")
      (node (ref "R33") (pin "2") (pinfunction "2_2") (pintype "passive"))
    )
    (net (code "219") (name "unconnected-(R34-Pad2)") (class "Default")
      (node (ref "R34") (pin "2") (pinfunction "2_2") (pintype "passive"))
    )
    (net (code "220") (name "unconnected-(R35-Pad2)") (class "Default")
      (node (ref "R35") (pin "2") (pinfunction "2_2") (pintype "passive"))
    )
    (net (code "221") (name "unconnected-(R36-Pad2)") (class "Default")
      (node (ref "R36") (pin "2") (pinfunction "2_2") (pintype "passive"))
    )
    (net (code "222") (name "unconnected-(R37-Pad2)") (class "Default")
      (node (ref "R37") (pin "2") (pinfunction "2_2") (pintype "passive"))
    )
    (net (code "223") (name "unconnected-(R38-Pad2)") (class "Default")
      (node (ref "R38") (pin "2") (pinfunction "2_2") (pintype "passive"))
    )
    (net (code "224") (name "unconnected-(R39-Pad2)") (class "Default")
      (node (ref "R39") (pin "2") (pinfunction "2_2") (pintype "passive"))
    )
    (net (code "225") (name "unconnected-(R40-Pad2)") (class "Default")
      (node (ref "R40") (pin "2") (pinfunction "2_2") (pintype "passive"))
    )
    (net (code "226") (name "unconnected-(R41-Pad2)") (class "Default")
      (node (ref "R41") (pin "2") (pinfunction "2_2") (pintype "passive"))
    )
    (net (code "227") (name "unconnected-(R42-Pad2)") (class "Default")
      (node (ref "R42") (pin "2") (pinfunction "2_2") (pintype "passive"))
    )
    (net (code "228") (name "unconnected-(R43-Pad2)") (class "Default")
      (node (ref "R43") (pin "2") (pinfunction "2_2") (pintype "passive"))
    )
    (net (code "229") (name "unconnected-(R44-Pad2)") (class "Default")
      (node (ref "R44") (pin "2") (pinfunction "2_2") (pintype "passive"))
    )
    (net (code "230") (name "unconnected-(R45-Pad2)") (class "Default")
      (node (ref "R45") (pin "2") (pinfunction "2_2") (pintype "passive"))
    )
    (net (code "231") (name "unconnected-(R46-Pad2)") (class "Default")
      (node (ref "R46") (pin "2") (pinfunction "2_2") (pintype "passive"))
    )
    (net (code "232") (name "unconnected-(R47-Pad1)") (class "Default")
      (node (ref "R47") (pin "1") (pinfunction "1_1") (pintype "passive"))
    )
    (net (code "233") (name "unconnected-(R47-Pad2)") (class "Default")
      (node (ref "R47") (pin "2") (pinfunction "2_2") (pintype "passive"))
    )
    (net (code "234") (name "unconnected-(R48-Pad1)") (class "Default")
      (node (ref "R48") (pin "1") (pinfunction "1_1") (pintype "passive"))
    )
    (net (code "235") (name "unconnected-(R48-Pad2)") (class "Default")
      (node (ref "R48") (pin "2") (pinfunction "2_2") (pintype "passive"))
    )
    (net (code "236") (name "unconnected-(R51-Pad2)") (class "Default")
      (node (ref "R51") (pin "2") (pinfunction "2_2") (pintype "passive"))
    )
    (net (code "237") (name "unconnected-(R52-Pad2)") (class "Default")
      (node (ref "R52") (pin "2") (pinfunction "2_2") (pintype "passive"))
    )
    (net (code "238") (name "unconnected-(R53-Pad2)") (class "Default")
      (node (ref "R53") (pin "2") (pinfunction "2_2") (pintype "passive"))
    )
    (net (code "239") (name "unconnected-(R54-Pad2)") (class "Default")
      (node (ref "R54") (pin "2") (pinfunction "2_2") (pintype "passive"))
    )
    (net (code "240") (name "unconnected-(R55-Pad2)") (class "Default")
      (node (ref "R55") (pin "2") (pinfunction "2_2") (pintype "passive"))
    )
    (net (code "241") (name "unconnected-(R56-Pad2)") (class "Default")
      (node (ref "R56") (pin "2") (pinfunction "2_2") (pintype "passive"))
    )
    (net (code "242") (name "unconnected-(R57-Pad2)") (class "Default")
      (node (ref "R57") (pin "2") (pinfunction "2_2") (pintype "passive"))
    )
    (net (code "243") (name "unconnected-(R58-Pad2)") (class "Default")
      (node (ref "R58") (pin "2") (pinfunction "2_2") (pintype "passive"))
    )
    (net (code "244") (name "unconnected-(R59-Pad2)") (class "Default")
      (node (ref "R59") (pin "2") (pinfunction "2_2") (pintype "passive"))
    )
    (net (code "245") (name "unconnected-(R60-Pad2)") (class "Default")
      (node (ref "R60") (pin "2") (pinfunction "2_2") (pintype "passive"))
    )
    (net (code "246") (name "unconnected-(R61-Pad2)") (class "Default")
      (node (ref "R61") (pin "2") (pinfunction "2_2") (pintype "passive"))
    )
    (net (code "247") (name "unconnected-(R62-Pad2)") (class "Default")
      (node (ref "R62") (pin "2") (pinfunction "2_2") (pintype "passive"))
    )
    (net (code "248") (name "unconnected-(R63-Pad2)") (class "Default")
      (node (ref "R63") (pin "2") (pinfunction "2_2") (pintype "passive"))
    )
    (net (code "249") (name "unconnected-(R64-Pad2)") (class "Default")
      (node (ref "R64") (pin "2") (pinfunction "2_2") (pintype "passive"))
    )
    (net (code "250") (name "unconnected-(R65-Pad2)") (class "Default")
      (node (ref "R65") (pin "2") (pinfunction "2_2") (pintype "passive"))
    )
    (net (code "251") (name "unconnected-(R66-Pad2)") (class "Default")
      (node (ref "R66") (pin "2") (pinfunction "2_2") (pintype "passive"))
    )
    (net (code "252") (name "unconnected-(U8-A0-Pad2)") (class "Default")
      (node (ref "U8") (pin "2") (pinfunction "A0_2") (pintype "bidirectional"))
    )
    (net (code "253") (name "unconnected-(U8-A1-Pad3)") (class "Default")
      (node (ref "U8") (pin "3") (pinfunction "A1_3") (pintype "bidirectional"))
    )
    (net (code "254") (name "unconnected-(U8-A2-Pad4)") (class "Default")
      (node (ref "U8") (pin "4") (pinfunction "A2_4") (pintype "bidirectional"))
    )
    (net (code "255") (name "unconnected-(U8-A3-Pad5)") (class "Default")
      (node (ref "U8") (pin "5") (pinfunction "A3_5") (pintype "bidirectional"))
    )
    (net (code "256") (name "unconnected-(U8-A4-Pad6)") (class "Default")
      (node (ref "U8") (pin "6") (pinfunction "A4_6") (pintype "bidirectional"))
    )
    (net (code "257") (name "unconnected-(U8-A5-Pad7)") (class "Default")
      (node (ref "U8") (pin "7") (pinfunction "A5_7") (pintype "bidirectional"))
    )
    (net (code "258") (name "unconnected-(U8-A6-Pad8)") (class "Default")
      (node (ref "U8") (pin "8") (pinfunction "A6_8") (pintype "bidirectional"))
    )
    (net (code "259") (name "unconnected-(U8-A7-Pad9)") (class "Default")
      (node (ref "U8") (pin "9") (pinfunction "A7_9") (pintype "bidirectional"))
    )
    (net (code "260") (name "unconnected-(U8-B0-Pad18)") (class "Default")
      (node (ref "U8") (pin "18") (pinfunction "B0_18") (pintype "bidirectional"))
    )
    (net (code "261") (name "unconnected-(U8-B1-Pad17)") (class "Default")
      (node (ref "U8") (pin "17") (pinfunction "B1_17") (pintype "bidirectional"))
    )
    (net (code "262") (name "unconnected-(U8-B2-Pad16)") (class "Default")
      (node (ref "U8") (pin "16") (pinfunction "B2_16") (pintype "bidirectional"))
    )
    (net (code "263") (name "unconnected-(U8-B3-Pad15)") (class "Default")
      (node (ref "U8") (pin "15") (pinfunction "B3_15") (pintype "bidirectional"))
    )
    (net (code "264") (name "unconnected-(U8-B4-Pad14)") (class "Default")
      (node (ref "U8") (pin "14") (pinfunction "B4_14") (pintype "bidirectional"))
    )
    (net (code "265") (name "unconnected-(U8-B5-Pad13)") (class "Default")
      (node (ref "U8") (pin "13") (pinfunction "B5_13") (pintype "bidirectional"))
    )
    (net (code "266") (name "unconnected-(U8-B6-Pad12)") (class "Default")
      (node (ref "U8") (pin "12") (pinfunction "B6_12") (pintype "bidirectional"))
    )
    (net (code "267") (name "unconnected-(U8-B7-Pad11)") (class "Default")
      (node (ref "U8") (pin "11") (pinfunction "B7_11") (pintype "bidirectional"))
    )
    (net (code "268") (name "unconnected-(U8-GND-Pad10)") (class "Default")
      (node (ref "U8") (pin "10") (pinfunction "GND_10") (pintype "power_in"))
    )
    (net (code "269") (name "unconnected-(U8-T{slash}~{R}-Pad1)") (class "Default")
      (node (ref "U8") (pin "1") (pinfunction "T/~{R}_1") (pintype "input"))
    )
    (net (code "270") (name "unconnected-(U8-VCC-Pad20)") (class "Default")
      (node (ref "U8") (pin "20") (pinfunction "VCC_20") (pintype "power_in"))
    )
    (net (code "271") (name "unconnected-(U8-~{OE}-Pad19)") (class "Default")
      (node (ref "U8") (pin "19") (pinfunction "~{OE}_19") (pintype "input"))
    )
    (net (code "272") (name "unconnected-(U9-A0-Pad2)") (class "Default")
      (node (ref "U9") (pin "2") (pinfunction "A0_2") (pintype "bidirectional"))
    )
    (net (code "273") (name "unconnected-(U9-A1-Pad3)") (class "Default")
      (node (ref "U9") (pin "3") (pinfunction "A1_3") (pintype "bidirectional"))
    )
    (net (code "274") (name "unconnected-(U9-A2-Pad4)") (class "Default")
      (node (ref "U9") (pin "4") (pinfunction "A2_4") (pintype "bidirectional"))
    )
    (net (code "275") (name "unconnected-(U9-A3-Pad5)") (class "Default")
      (node (ref "U9") (pin "5") (pinfunction "A3_5") (pintype "bidirectional"))
    )
    (net (code "276") (name "unconnected-(U9-A4-Pad6)") (class "Default")
      (node (ref "U9") (pin "6") (pinfunction "A4_6") (pintype "bidirectional"))
    )
    (net (code "277") (name "unconnected-(U9-A5-Pad7)") (class "Default")
      (node (ref "U9") (pin "7") (pinfunction "A5_7") (pintype "bidirectional"))
    )
    (net (code "278") (name "unconnected-(U9-A6-Pad8)") (class "Default")
      (node (ref "U9") (pin "8") (pinfunction "A6_8") (pintype "bidirectional"))
    )
    (net (code "279") (name "unconnected-(U9-A7-Pad9)") (class "Default")
      (node (ref "U9") (pin "9") (pinfunction "A7_9") (pintype "bidirectional"))
    )
    (net (code "280") (name "unconnected-(U9-B0-Pad18)") (class "Default")
      (node (ref "U9") (pin "18") (pinfunction "B0_18") (pintype "bidirectional"))
    )
    (net (code "281") (name "unconnected-(U9-B1-Pad17)") (class "Default")
      (node (ref "U9") (pin "17") (pinfunction "B1_17") (pintype "bidirectional"))
    )
    (net (code "282") (name "unconnected-(U9-B2-Pad16)") (class "Default")
      (node (ref "U9") (pin "16") (pinfunction "B2_16") (pintype "bidirectional"))
    )
    (net (code "283") (name "unconnected-(U9-B3-Pad15)") (class "Default")
      (node (ref "U9") (pin "15") (pinfunction "B3_15") (pintype "bidirectional"))
    )
    (net (code "284") (name "unconnected-(U9-B4-Pad14)") (class "Default")
      (node (ref "U9") (pin "14") (pinfunction "B4_14") (pintype "bidirectional"))
    )
    (net (code "285") (name "unconnected-(U9-B5-Pad13)") (class "Default")
      (node (ref "U9") (pin "13") (pinfunction "B5_13") (pintype "bidirectional"))
    )
    (net (code "286") (name "unconnected-(U9-B6-Pad12)") (class "Default")
      (node (ref "U9") (pin "12") (pinfunction "B6_12") (pintype "bidirectional"))
    )
    (net (code "287") (name "unconnected-(U9-B7-Pad11)") (class "Default")
      (node (ref "U9") (pin "11") (pinfunction "B7_11") (pintype "bidirectional"))
    )
    (net (code "288") (name "unconnected-(U9-GND-Pad10)") (class "Default")
      (node (ref "U9") (pin "10") (pinfunction "GND_10") (pintype "power_in"))
    )
    (net (code "289") (name "unconnected-(U9-T{slash}~{R}-Pad1)") (class "Default")
      (node (ref "U9") (pin "1") (pinfunction "T/~{R}_1") (pintype "input"))
    )
    (net (code "290") (name "unconnected-(U9-VCC-Pad20)") (class "Default")
      (node (ref "U9") (pin "20") (pinfunction "VCC_20") (pintype "power_in"))
    )
    (net (code "291") (name "unconnected-(U9-~{OE}-Pad19)") (class "Default")
      (node (ref "U9") (pin "19") (pinfunction "~{OE}_19") (pintype "input"))
    )
    (net (code "292") (name "unconnected-(U10-A0-Pad2)") (class "Default")
      (node (ref "U10") (pin "2") (pinfunction "A0_2") (pintype "bidirectional"))
    )
    (net (code "293") (name "unconnected-(U10-A1-Pad3)") (class "Default")
      (node (ref "U10") (pin "3") (pinfunction "A1_3") (pintype "bidirectional"))
    )
    (net (code "294") (name "unconnected-(U10-A2-Pad4)") (class "Default")
      (node (ref "U10") (pin "4") (pinfunction "A2_4") (pintype "bidirectional"))
    )
    (net (code "295") (name "unconnected-(U10-A3-Pad5)") (class "Default")
      (node (ref "U10") (pin "5") (pinfunction "A3_5") (pintype "bidirectional"))
    )
    (net (code "296") (name "unconnected-(U10-A4-Pad6)") (class "Default")
      (node (ref "U10") (pin "6") (pinfunction "A4_6") (pintype "bidirectional"))
    )
    (net (code "297") (name "unconnected-(U10-A5-Pad7)") (class "Default")
      (node (ref "U10") (pin "7") (pinfunction "A5_7") (pintype "bidirectional"))
    )
    (net (code "298") (name "unconnected-(U10-A6-Pad8)") (class "Default")
      (node (ref "U10") (pin "8") (pinfunction "A6_8") (pintype "bidirectional"))
    )
    (net (code "299") (name "unconnected-(U10-A7-Pad9)") (class "Default")
      (node (ref "U10") (pin "9") (pinfunction "A7_9") (pintype "bidirectional"))
    )
    (net (code "300") (name "unconnected-(U10-B0-Pad18)") (class "Default")
      (node (ref "U10") (pin "18") (pinfunction "B0_18") (pintype "bidirectional"))
    )
    (net (code "301") (name "unconnected-(U10-B1-Pad17)") (class "Default")
      (node (ref "U10") (pin "17") (pinfunction "B1_17") (pintype "bidirectional"))
    )
    (net (code "302") (name "unconnected-(U10-B2-Pad16)") (class "Default")
      (node (ref "U10") (pin "16") (pinfunction "B2_16") (pintype "bidirectional"))
    )
    (net (code "303") (name "unconnected-(U10-B3-Pad15)") (class "Default")
      (node (ref "U10") (pin "15") (pinfunction "B3_15") (pintype "bidirectional"))
    )
    (net (code "304") (name "unconnected-(U10-B4-Pad14)") (class "Default")
      (node (ref "U10") (pin "14") (pinfunction "B4_14") (pintype "bidirectional"))
    )
    (net (code "305") (name "unconnected-(U10-B5-Pad13)") (class "Default")
      (node (ref "U10") (pin "13") (pinfunction "B5_13") (pintype "bidirectional"))
    )
    (net (code "306") (name "unconnected-(U10-B6-Pad12)") (class "Default")
      (node (ref "U10") (pin "12") (pinfunction "B6_12") (pintype "bidirectional"))
    )
    (net (code "307") (name "unconnected-(U10-B7-Pad11)") (class "Default")
      (node (ref "U10") (pin "11") (pinfunction "B7_11") (pintype "bidirectional"))
    )
    (net (code "308") (name "unconnected-(U10-GND-Pad10)") (class "Default")
      (node (ref "U10") (pin "10") (pinfunction "GND_10") (pintype "power_in"))
    )
    (net (code "309") (name "unconnected-(U10-T{slash}~{R}-Pad1)") (class "Default")
      (node (ref "U10") (pin "1") (pinfunction "T/~{R}_1") (pintype "input"))
    )
    (net (code "310") (name "unconnected-(U10-VCC-Pad20)") (class "Default")
      (node (ref "U10") (pin "20") (pinfunction "VCC_20") (pintype "power_in"))
    )
    (net (code "311") (name "unconnected-(U10-~{OE}-Pad19)") (class "Default")
      (node (ref "U10") (pin "19") (pinfunction "~{OE}_19") (pintype "input"))
    )
  )
)
